# cdf-teensy-interrupter.net
KiCad netlist of a schematic drawn in EAGLE
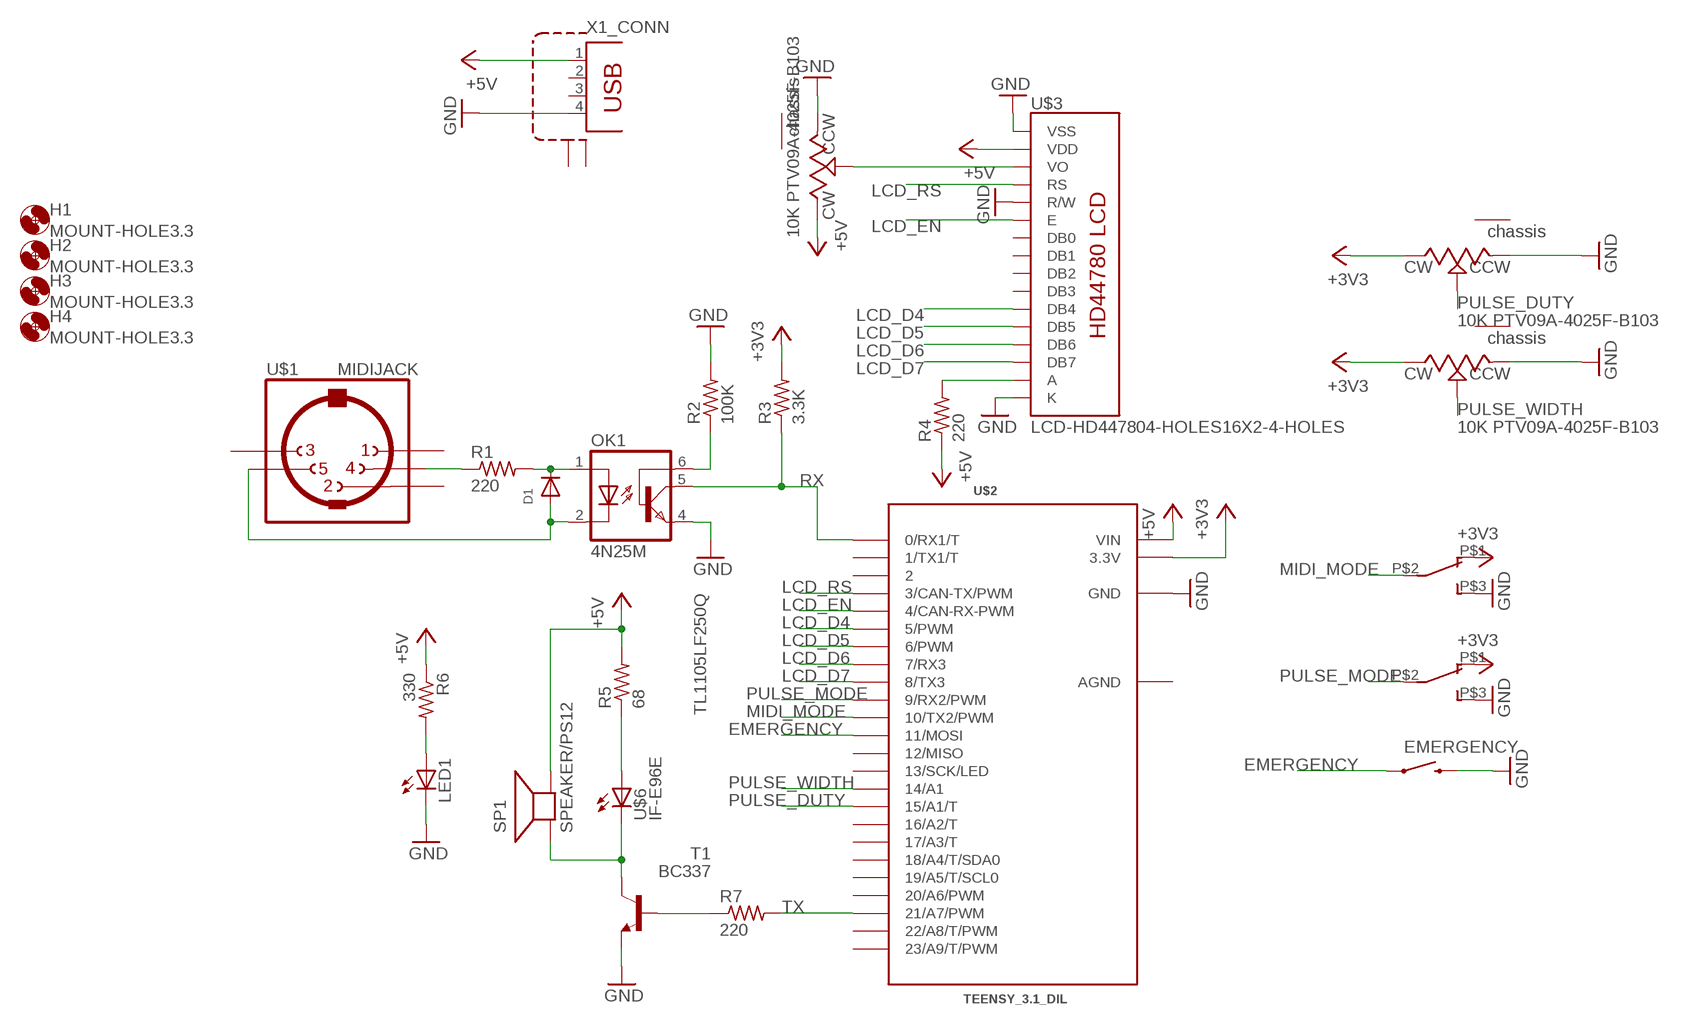
[diagram p0: schematic, sheet 1]

(export (version "E")
  (design (tool "Eeschema 10.0.6"))
  (components
    (comp (ref "D1")
      (value "DIODEDO-1N4148")
      (footprint "eagle-import:DO-1N4148")
      (libsource (lib "eagle-import") (part "DIODEDO-1N4148"))
    )
    (comp (ref "EMERGENCY")
      (value "SWITCH-MOMENTARY-2PTH")
      (footprint "eagle-import:TACTILE-PTH")
      (libsource (lib "eagle-import") (part "SWITCH-MOMENTARY-2PTH"))
    )
    (comp (ref "H1")
      (value "MOUNT-HOLE3.3")
      (footprint "eagle-import:3,3")
      (libsource (lib "eagle-import") (part "MOUNT-HOLE3.3"))
    )
    (comp (ref "H2")
      (value "MOUNT-HOLE3.3")
      (footprint "eagle-import:3,3")
      (libsource (lib "eagle-import") (part "MOUNT-HOLE3.3"))
    )
    (comp (ref "H3")
      (value "MOUNT-HOLE3.3")
      (footprint "eagle-import:3,3")
      (libsource (lib "eagle-import") (part "MOUNT-HOLE3.3"))
    )
    (comp (ref "H4")
      (value "MOUNT-HOLE3.3")
      (footprint "eagle-import:3,3")
      (libsource (lib "eagle-import") (part "MOUNT-HOLE3.3"))
    )
    (comp (ref "LCD_BL")
      (value "10K PTV09A-4025F-B103")
      (footprint "eagle-import:PTV09A-4")
      (libsource (lib "eagle-import") (part "POTENTIOMETERPTV09A_VERTICAL"))
    )
    (comp (ref "LED1")
      (value "LED5MM")
      (footprint "eagle-import:LED5MM")
      (libsource (lib "eagle-import") (part "LED5MM"))
    )
    (comp (ref "MIDI_MODE")
      (value "100SP1T1B4M2QE")
      (footprint "eagle-import:100SP1T1B4M2QE")
      (libsource (lib "eagle-import") (part "100SP1T1B4M2QE"))
    )
    (comp (ref "OK1")
      (value "4N25M")
      (footprint "eagle-import:DIL06")
      (fields (field (name "MPN") "4N25-M"))
      (libsource (lib "eagle-import") (part "4N?M25"))
    )
    (comp (ref "PULSE_DUTY")
      (value "10K PTV09A-4025F-B103")
      (footprint "eagle-import:PTV09A-4")
      (libsource (lib "eagle-import") (part "POTENTIOMETERPTV09A_VERTICAL"))
    )
    (comp (ref "PULSE_MODE")
      (value "100SP1T1B4M2QE")
      (footprint "eagle-import:100SP1T1B4M2QE")
      (libsource (lib "eagle-import") (part "100SP1T1B4M2QE"))
    )
    (comp (ref "PULSE_WIDTH")
      (value "10K PTV09A-4025F-B103")
      (footprint "eagle-import:PTV09A-4")
      (libsource (lib "eagle-import") (part "POTENTIOMETERPTV09A_VERTICAL"))
    )
    (comp (ref "R1")
      (value "220")
      (footprint "eagle-import:0204_7")
      (libsource (lib "eagle-import") (part "R-US_0204/7"))
    )
    (comp (ref "R2")
      (value "100K")
      (footprint "eagle-import:0204_7")
      (libsource (lib "eagle-import") (part "R-US_0204/7"))
    )
    (comp (ref "R3")
      (value "3.3K")
      (footprint "eagle-import:0204_7")
      (libsource (lib "eagle-import") (part "R-US_0204/7"))
    )
    (comp (ref "R4")
      (value "220")
      (footprint "eagle-import:0204_7")
      (libsource (lib "eagle-import") (part "R-US_0204/7"))
    )
    (comp (ref "R5")
      (value "68")
      (footprint "eagle-import:0204_7")
      (libsource (lib "eagle-import") (part "R-US_0204/7"))
    )
    (comp (ref "R6")
      (value "330")
      (footprint "eagle-import:0204_7")
      (libsource (lib "eagle-import") (part "R-US_0204/7"))
    )
    (comp (ref "R7")
      (value "220")
      (footprint "eagle-import:0204_7")
      (libsource (lib "eagle-import") (part "R-US_0204/7"))
    )
    (comp (ref "SP1")
      (value "SPEAKER/PS12")
      (footprint "eagle-import:PS12")
      (libsource (lib "eagle-import") (part "SPEAKER/PS12"))
    )
    (comp (ref "T1")
      (value "BC337")
      (footprint "eagle-import:TO92")
      (libsource (lib "eagle-import") (part "BC337"))
    )
    (comp (ref "U$1")
      (value "MIDIJACK")
      (footprint "eagle-import:CP-2350")
      (libsource (lib "eagle-import") (part "MIDIJACK"))
    )
    (comp (ref "U$2")
      (value "TEENSY_3.1_DIL")
      (footprint "eagle-import:TEENSY3-DIL")
      (libsource (lib "eagle-import") (part "TEENSY_3.1_DIL"))
    )
    (comp (ref "U$3")
      (value "LCD-HD447804-HOLES16X2-4-HOLES")
      (footprint "eagle-import:LCD-16X2-4HOLES")
      (libsource (lib "eagle-import") (part "LCD-HD4478016X2-4-HOLES4-HOLES"))
    )
    (comp (ref "U$6")
      (value "IF-E96E")
      (footprint "eagle-import:IF-E96E")
      (libsource (lib "eagle-import") (part "IF-E96E"))
    )
    (comp (ref "X1")
      (value "TE-292304-1")
      (footprint "eagle-import:TE-292304-1")
      (fields (field (name "MPN") "292304-1 "))
      (libsource (lib "eagle-import") (part "TE-292304-1"))
    )
  )
  (nets
    (net (code "1") (name "+3V3") (class "Default")
      (node (ref "MIDI_MODE") (pin "P$1") (pinfunction "1_P$1") (pintype "passive"))
      (node (ref "PULSE_DUTY") (pin "3") (pinfunction "CW_3") (pintype "passive"))
      (node (ref "PULSE_MODE") (pin "P$1") (pinfunction "1_P$1") (pintype "passive"))
      (node (ref "PULSE_WIDTH") (pin "3") (pinfunction "CW_3") (pintype "passive"))
      (node (ref "R3") (pin "2") (pinfunction "2_2") (pintype "passive"))
      (node (ref "U$2") (pin "3.3V") (pinfunction "3.3V_3.3V") (pintype "power_in"))
    )
    (net (code "2") (name "+5V") (class "Default")
      (node (ref "LCD_BL") (pin "3") (pinfunction "CW_3") (pintype "passive"))
      (node (ref "R4") (pin "1") (pinfunction "1_1") (pintype "passive"))
      (node (ref "R5") (pin "2") (pinfunction "2_2") (pintype "passive"))
      (node (ref "R6") (pin "1") (pinfunction "1_1") (pintype "passive"))
      (node (ref "SP1") (pin "P$2") (pinfunction "-_P$2") (pintype "passive"))
      (node (ref "U$2") (pin "VIN") (pinfunction "VIN_VIN") (pintype "power_in"))
      (node (ref "U$3") (pin "2") (pinfunction "VDD_2") (pintype "power_in"))
      (node (ref "X1") (pin "1") (pinfunction "1_1") (pintype "bidirectional"))
    )
    (net (code "3") (name "/AGND") (class "Default")
      (node (ref "U$2") (pin "AGND") (pinfunction "AGND_AGND") (pintype "power_in"))
    )
    (net (code "4") (name "/EMERGENCY") (class "Default")
      (node (ref "EMERGENCY") (pin "1") (pinfunction "1_1") (pintype "passive"))
      (node (ref "U$2") (pin "11") (pinfunction "11/MOSI_11") (pintype "bidirectional"))
    )
    (net (code "5") (name "/LCD_D4") (class "Default")
      (node (ref "U$2") (pin "5") (pinfunction "5/PWM_5") (pintype "bidirectional"))
      (node (ref "U$3") (pin "11") (pinfunction "DB4_11") (pintype "bidirectional"))
    )
    (net (code "6") (name "/LCD_D5") (class "Default")
      (node (ref "U$2") (pin "6") (pinfunction "6/PWM_6") (pintype "bidirectional"))
      (node (ref "U$3") (pin "12") (pinfunction "DB5_12") (pintype "bidirectional"))
    )
    (net (code "7") (name "/LCD_D6") (class "Default")
      (node (ref "U$2") (pin "7") (pinfunction "7/RX3_7") (pintype "bidirectional"))
      (node (ref "U$3") (pin "13") (pinfunction "DB6_13") (pintype "bidirectional"))
    )
    (net (code "8") (name "/LCD_D7") (class "Default")
      (node (ref "U$2") (pin "8") (pinfunction "8/TX3_8") (pintype "bidirectional"))
      (node (ref "U$3") (pin "14") (pinfunction "DB7_14") (pintype "bidirectional"))
    )
    (net (code "9") (name "/LCD_EN") (class "Default")
      (node (ref "U$2") (pin "4") (pinfunction "4/CAN-RX-PWM_4") (pintype "bidirectional"))
      (node (ref "U$3") (pin "6") (pinfunction "E_6") (pintype "input"))
    )
    (net (code "10") (name "/LCD_RS") (class "Default")
      (node (ref "U$2") (pin "3") (pinfunction "3/CAN-TX/PWM_3") (pintype "bidirectional"))
      (node (ref "U$3") (pin "4") (pinfunction "RS_4") (pintype "input"))
    )
    (net (code "11") (name "/MIDI_MODE") (class "Default")
      (node (ref "MIDI_MODE") (pin "P$2") (pinfunction "2_P$2") (pintype "passive"))
      (node (ref "U$2") (pin "10") (pinfunction "10/TX2/PWM_10") (pintype "bidirectional"))
    )
    (net (code "12") (name "/PULSE_DUTY") (class "Default")
      (node (ref "PULSE_DUTY") (pin "2") (pinfunction "WIPER_2") (pintype "passive"))
      (node (ref "U$2") (pin "15/A1") (pinfunction "15/A1/T_15/A1") (pintype "bidirectional"))
    )
    (net (code "13") (name "/PULSE_MODE") (class "Default")
      (node (ref "PULSE_MODE") (pin "P$2") (pinfunction "2_P$2") (pintype "passive"))
      (node (ref "U$2") (pin "9") (pinfunction "9/RX2/PWM_9") (pintype "bidirectional"))
    )
    (net (code "14") (name "/PULSE_WIDTH") (class "Default")
      (node (ref "PULSE_WIDTH") (pin "2") (pinfunction "WIPER_2") (pintype "passive"))
      (node (ref "U$2") (pin "14/A0") (pinfunction "14/A1_14/A0") (pintype "bidirectional"))
    )
    (net (code "15") (name "/RX") (class "Default")
      (node (ref "OK1") (pin "5") (pinfunction "COL_5") (pintype "passive"))
      (node (ref "R3") (pin "1") (pinfunction "1_1") (pintype "passive"))
      (node (ref "U$2") (pin "0") (pinfunction "0/RX1/T_0") (pintype "bidirectional"))
    )
    (net (code "16") (name "/TX") (class "Default")
      (node (ref "R7") (pin "2") (pinfunction "2_2") (pintype "passive"))
      (node (ref "U$2") (pin "21/A7") (pinfunction "21/A7/PWM_21/A7") (pintype "bidirectional"))
    )
    (net (code "17") (name "GND") (class "Default")
      (node (ref "EMERGENCY") (pin "3") (pinfunction "2_3") (pintype "passive"))
      (node (ref "LCD_BL") (pin "1") (pinfunction "CCW_1") (pintype "passive"))
      (node (ref "LED1") (pin "K") (pinfunction "C_K") (pintype "passive"))
      (node (ref "MIDI_MODE") (pin "P$3") (pinfunction "3_P$3") (pintype "passive"))
      (node (ref "OK1") (pin "4") (pinfunction "EMI_4") (pintype "passive"))
      (node (ref "PULSE_DUTY") (pin "1") (pinfunction "CCW_1") (pintype "passive"))
      (node (ref "PULSE_MODE") (pin "P$3") (pinfunction "3_P$3") (pintype "passive"))
      (node (ref "PULSE_WIDTH") (pin "1") (pinfunction "CCW_1") (pintype "passive"))
      (node (ref "R2") (pin "2") (pinfunction "2_2") (pintype "passive"))
      (node (ref "T1") (pin "1") (pinfunction "E_1") (pintype "passive"))
      (node (ref "U$2") (pin "GND") (pinfunction "GND_GND") (pintype "power_in"))
      (node (ref "U$3") (pin "1") (pinfunction "VSS_1") (pintype "power_in"))
      (node (ref "U$3") (pin "16") (pinfunction "K_16") (pintype "power_in"))
      (node (ref "U$3") (pin "5") (pinfunction "R/W_5") (pintype "input"))
      (node (ref "X1") (pin "4") (pinfunction "4_4") (pintype "bidirectional"))
    )
    (net (code "18") (name "Net-(LCD_BL-WIPER)") (class "Default")
      (node (ref "LCD_BL") (pin "2") (pinfunction "WIPER_2") (pintype "passive"))
      (node (ref "U$3") (pin "3") (pinfunction "VO_3") (pintype "bidirectional"))
    )
    (net (code "19") (name "Net-(LED1-PadA)") (class "Default")
      (node (ref "LED1") (pin "A") (pinfunction "A_A") (pintype "passive"))
      (node (ref "R6") (pin "2") (pinfunction "2_2") (pintype "passive"))
    )
    (net (code "20") (name "Net-(OK1-A)") (class "Default")
      (node (ref "D1") (pin "C") (pinfunction "C_C") (pintype "passive"))
      (node (ref "OK1") (pin "1") (pinfunction "A_1") (pintype "passive"))
      (node (ref "R1") (pin "2") (pinfunction "2_2") (pintype "passive"))
    )
    (net (code "21") (name "Net-(OK1-BAS)") (class "Default")
      (node (ref "OK1") (pin "6") (pinfunction "BAS_6") (pintype "passive"))
      (node (ref "R2") (pin "1") (pinfunction "1_1") (pintype "passive"))
    )
    (net (code "22") (name "Net-(OK1-C)") (class "Default")
      (node (ref "D1") (pin "A") (pinfunction "A_A") (pintype "passive"))
      (node (ref "OK1") (pin "2") (pinfunction "C_2") (pintype "passive"))
      (node (ref "U$1") (pin "5") (pinfunction "5_5") (pintype "passive"))
    )
    (net (code "23") (name "Net-(R1-Pad1)") (class "Default")
      (node (ref "R1") (pin "1") (pinfunction "1_1") (pintype "passive"))
      (node (ref "U$1") (pin "4") (pinfunction "4_4") (pintype "passive"))
    )
    (net (code "24") (name "Net-(SP1-+)") (class "Default")
      (node (ref "SP1") (pin "P$1") (pinfunction "+_P$1") (pintype "passive"))
      (node (ref "T1") (pin "3") (pinfunction "C_3") (pintype "passive"))
      (node (ref "U$6") (pin "P$1_CATHODE-") (pinfunction "C_P$1_CATHODE-") (pintype "passive"))
    )
    (net (code "25") (name "Net-(T1-B)") (class "Default")
      (node (ref "R7") (pin "1") (pinfunction "1_1") (pintype "passive"))
      (node (ref "T1") (pin "2") (pinfunction "B_2") (pintype "passive"))
    )
    (net (code "26") (name "Net-(U$3-A)") (class "Default")
      (node (ref "R4") (pin "2") (pinfunction "2_2") (pintype "passive"))
      (node (ref "U$3") (pin "15") (pinfunction "A_15") (pintype "power_in"))
    )
    (net (code "27") (name "Net-(U$6-A)") (class "Default")
      (node (ref "R5") (pin "1") (pinfunction "1_1") (pintype "passive"))
      (node (ref "U$6") (pin "P$2_ANODE+") (pinfunction "A_P$2_ANODE+") (pintype "passive"))
    )
    (net (code "28") (name "unconnected-(LCD_BL-CHASSIS-Pad4)") (class "Default")
      (node (ref "LCD_BL") (pin "4") (pinfunction "CHASSIS_4") (pintype "passive"))
    )
    (net (code "29") (name "unconnected-(PULSE_DUTY-CHASSIS-Pad4)") (class "Default")
      (node (ref "PULSE_DUTY") (pin "4") (pinfunction "CHASSIS_4") (pintype "passive"))
    )
    (net (code "30") (name "unconnected-(PULSE_WIDTH-CHASSIS-Pad4)") (class "Default")
      (node (ref "PULSE_WIDTH") (pin "4") (pinfunction "CHASSIS_4") (pintype "passive"))
    )
    (net (code "31") (name "unconnected-(U$1-Pad1)") (class "Default")
      (node (ref "U$1") (pin "1") (pinfunction "1_1") (pintype "passive"))
    )
    (net (code "32") (name "unconnected-(U$1-Pad2)") (class "Default")
      (node (ref "U$1") (pin "2") (pinfunction "2_2") (pintype "passive"))
    )
    (net (code "33") (name "unconnected-(U$1-Pad3)") (class "Default")
      (node (ref "U$1") (pin "3") (pinfunction "3_3") (pintype "passive"))
    )
    (net (code "34") (name "unconnected-(U$2-1{slash}TX1{slash}T-Pad1)") (class "Default")
      (node (ref "U$2") (pin "1") (pinfunction "1/TX1/T_1") (pintype "bidirectional"))
    )
    (net (code "35") (name "unconnected-(U$2-12{slash}MISO-Pad12)") (class "Default")
      (node (ref "U$2") (pin "12") (pinfunction "12/MISO_12") (pintype "bidirectional"))
    )
    (net (code "36") (name "unconnected-(U$2-13{slash}SCK{slash}LED-Pad13)") (class "Default")
      (node (ref "U$2") (pin "13") (pinfunction "13/SCK/LED_13") (pintype "bidirectional"))
    )
    (net (code "37") (name "unconnected-(U$2-16{slash}A2{slash}T-Pad16{slash}A2)") (class "Default")
      (node (ref "U$2") (pin "16/A2") (pinfunction "16/A2/T_16/A2") (pintype "bidirectional"))
    )
    (net (code "38") (name "unconnected-(U$2-17{slash}A3{slash}T-Pad17{slash}A3)") (class "Default")
      (node (ref "U$2") (pin "17/A3") (pinfunction "17/A3/T_17/A3") (pintype "bidirectional"))
    )
    (net (code "39") (name "unconnected-(U$2-18{slash}A4{slash}T{slash}SDA0-Pad18{slash}A4)") (class "Default")
      (node (ref "U$2") (pin "18/A4") (pinfunction "18/A4/T/SDA0_18/A4") (pintype "bidirectional"))
    )
    (net (code "40") (name "unconnected-(U$2-19{slash}A5{slash}T{slash}SCL0-Pad19{slash}A5)") (class "Default")
      (node (ref "U$2") (pin "19/A5") (pinfunction "19/A5/T/SCL0_19/A5") (pintype "bidirectional"))
    )
    (net (code "41") (name "unconnected-(U$2-20{slash}A6{slash}PWM-Pad20{slash}A6)") (class "Default")
      (node (ref "U$2") (pin "20/A6") (pinfunction "20/A6/PWM_20/A6") (pintype "bidirectional"))
    )
    (net (code "42") (name "unconnected-(U$2-22{slash}A8{slash}T{slash}PWM-Pad22{slash}A8)") (class "Default")
      (node (ref "U$2") (pin "22/A8") (pinfunction "22/A8/T/PWM_22/A8") (pintype "bidirectional"))
    )
    (net (code "43") (name "unconnected-(U$2-23{slash}A9{slash}T{slash}PWM-Pad23{slash}A9)") (class "Default")
      (node (ref "U$2") (pin "23/A9") (pinfunction "23/A9/T/PWM_23/A9") (pintype "bidirectional"))
    )
    (net (code "44") (name "unconnected-(U$2-Pad2)") (class "Default")
      (node (ref "U$2") (pin "2") (pinfunction "2_2") (pintype "bidirectional"))
    )
    (net (code "45") (name "unconnected-(U$3-DB0-Pad7)") (class "Default")
      (node (ref "U$3") (pin "7") (pinfunction "DB0_7") (pintype "bidirectional"))
    )
    (net (code "46") (name "unconnected-(U$3-DB1-Pad8)") (class "Default")
      (node (ref "U$3") (pin "8") (pinfunction "DB1_8") (pintype "bidirectional"))
    )
    (net (code "47") (name "unconnected-(U$3-DB2-Pad9)") (class "Default")
      (node (ref "U$3") (pin "9") (pinfunction "DB2_9") (pintype "bidirectional"))
    )
    (net (code "48") (name "unconnected-(U$3-DB3-Pad10)") (class "Default")
      (node (ref "U$3") (pin "10") (pinfunction "DB3_10") (pintype "bidirectional"))
    )
    (net (code "49") (name "unconnected-(X1-Pad2)") (class "Default")
      (node (ref "X1") (pin "2") (pinfunction "2_2") (pintype "bidirectional"))
    )
    (net (code "50") (name "unconnected-(X1-Pad3)") (class "Default")
      (node (ref "X1") (pin "3") (pinfunction "3_3") (pintype "bidirectional"))
    )
    (net (code "51") (name "unconnected-(X1A-S1-PadP$1)") (class "Default")
      (node (ref "X1") (pin "P$1") (pinfunction "S1_P$1") (pintype "passive"))
    )
    (net (code "52") (name "unconnected-(X1A-S2-PadP$2)") (class "Default")
      (node (ref "X1") (pin "P$2") (pinfunction "S2_P$2") (pintype "passive"))
    )
  )
)
